# SJ2088POE_LEFT_OV9282.net
KiCad netlist of a schematic drawn in Altium Designer
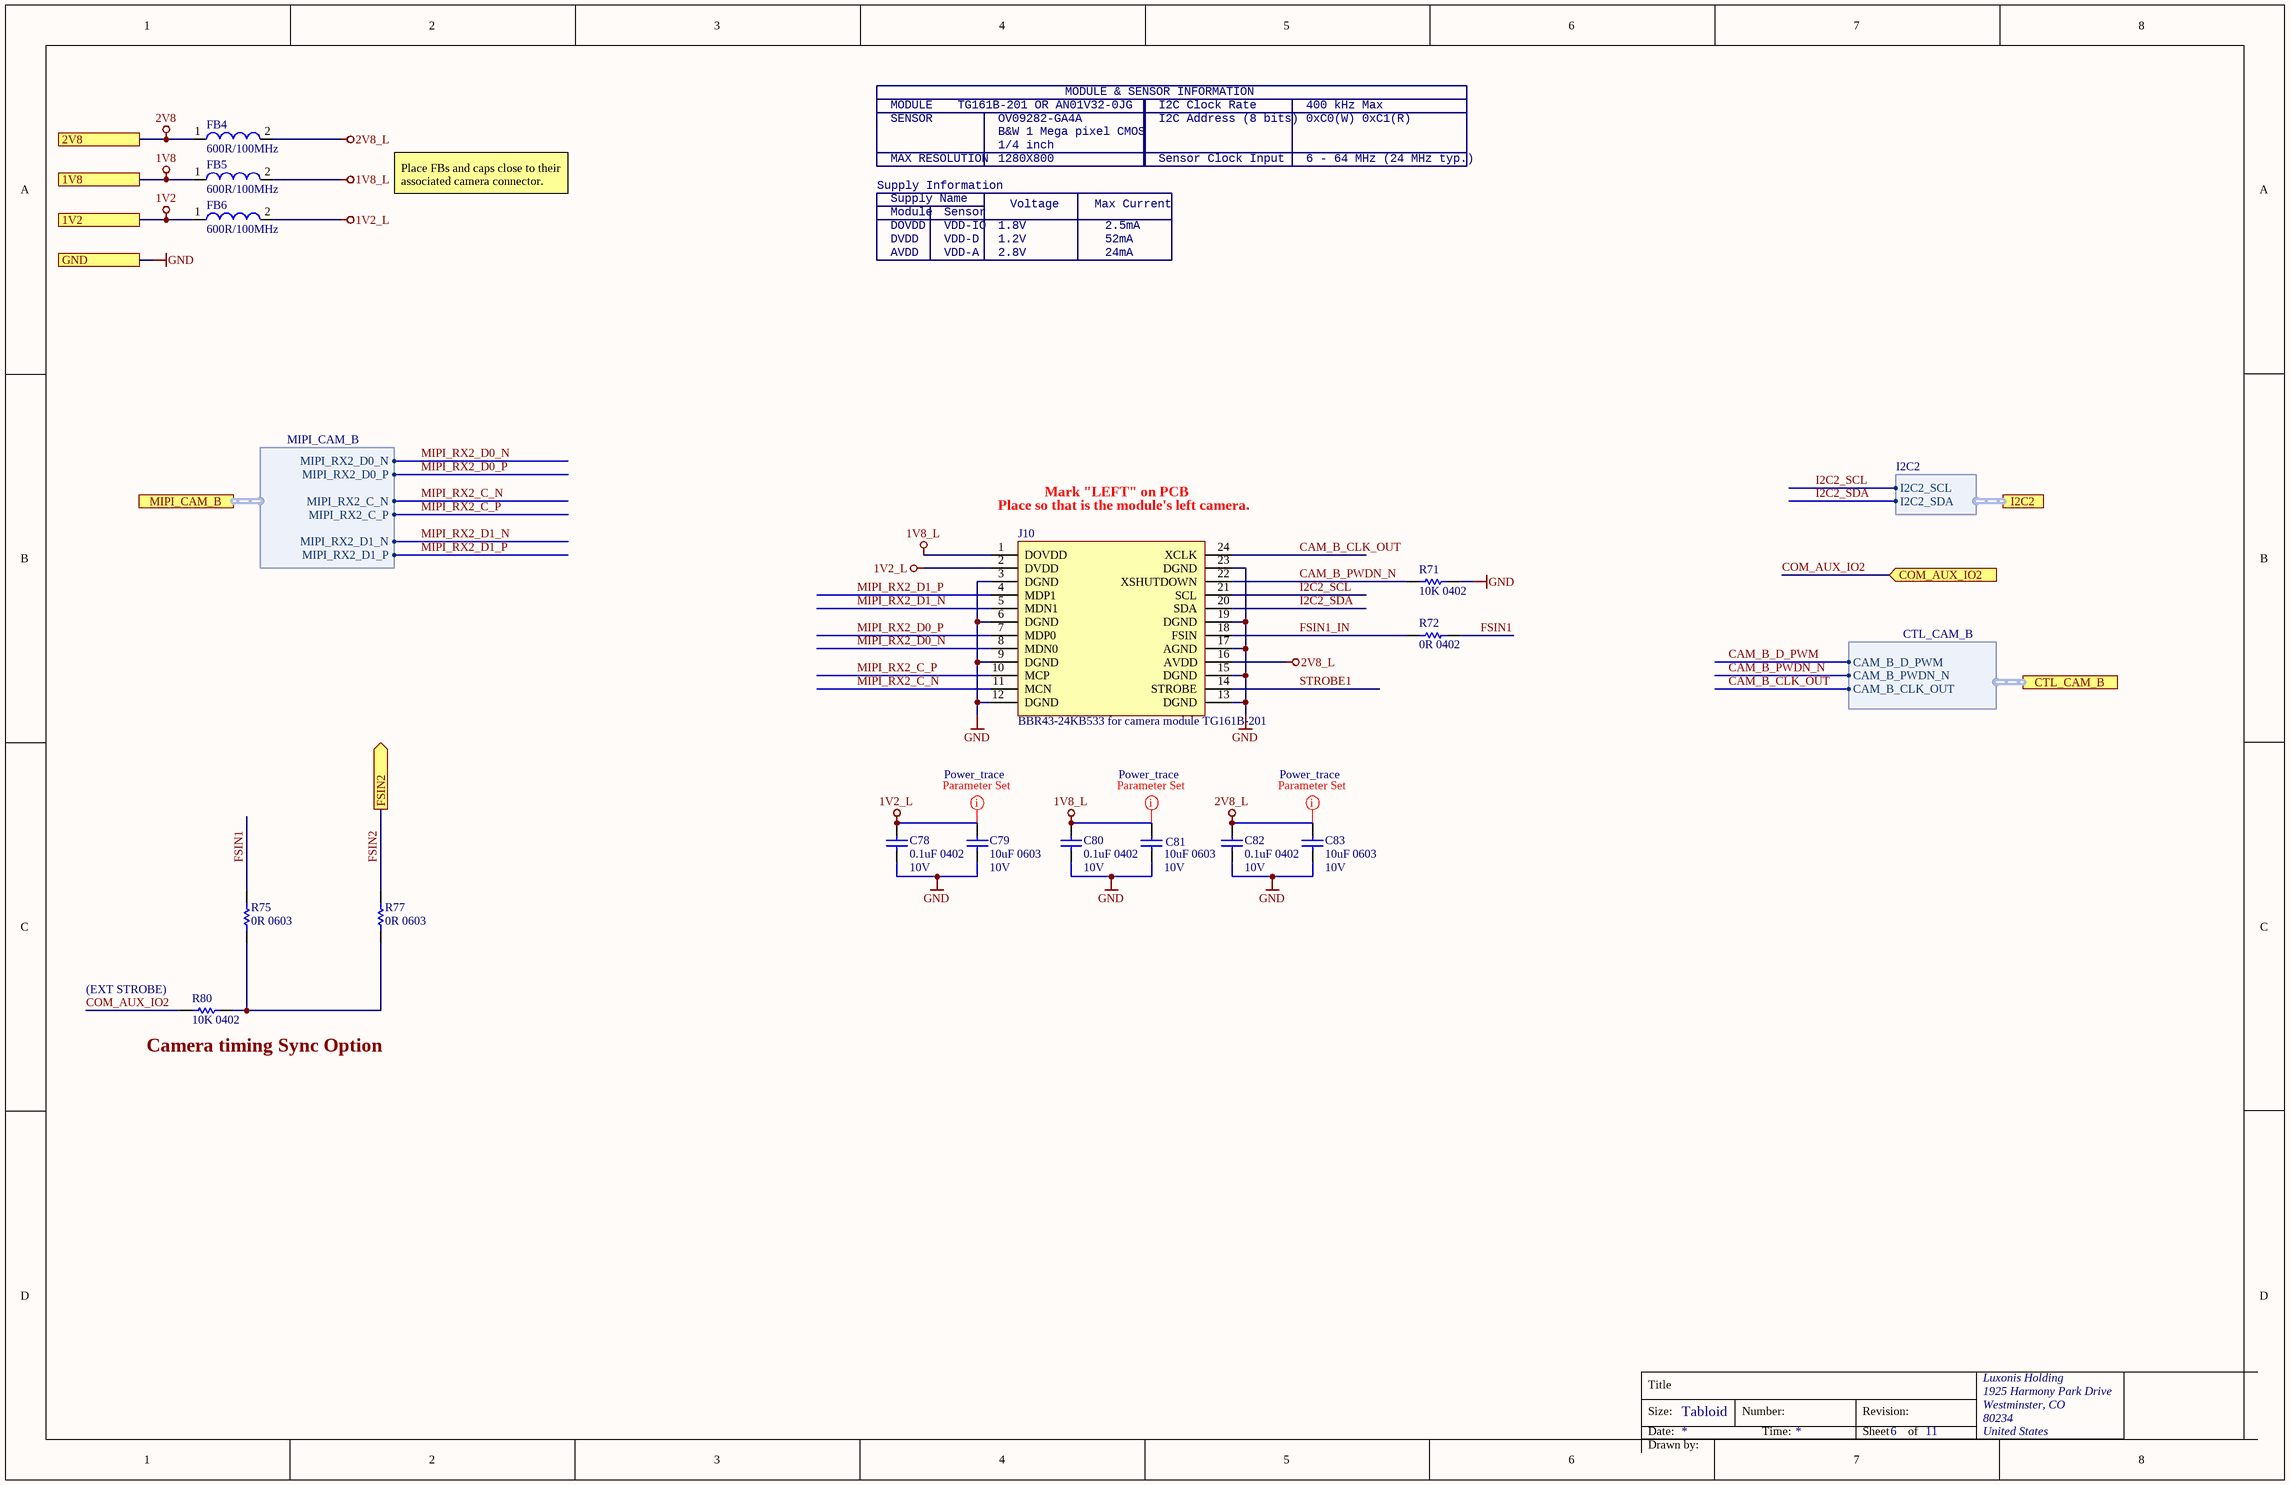
[diagram p0: SJ2088POE_LEFT_OV9282.SchDoc]

(export (version "E")
  (design (tool "Eeschema 10.0.6"))
  (components
    (comp (ref "C78")
      (value "0.1uF 0402")
      (footprint "CAP_Altium_Vault_Generic:CAPC0402(1005)70_L")
      (description "CAP CER 0.1UF 10V X7R 0402 5%")
      (fields (field (name "TOLERANCE") "5%") (field (name "VOLTAGE RATING") "10V"))
      (libsource (lib "LuxonisMaster") (part "GRM155R71A104JA01D"))
    )
    (comp (ref "C79")
      (value "10uF 0603")
      (footprint "CAP_Altium_Vault_Generic:CAPC0603(1608)100_L")
      (description "CAP CER 10UF 10V X5R 0603 20%")
      (fields (field (name "TOLERANCE") "20%") (field (name "VOLTAGE RATING") "10V"))
      (libsource (lib "LuxonisMaster") (part "GRM188R61A106ME69D"))
    )
    (comp (ref "C80")
      (value "0.1uF 0402")
      (footprint "CAP_Altium_Vault_Generic:CAPC0402(1005)70_L")
      (description "CAP CER 0.1UF 10V X7R 0402 5%")
      (fields (field (name "TOLERANCE") "5%") (field (name "VOLTAGE RATING") "10V"))
      (libsource (lib "LuxonisMaster") (part "GRM155R71A104JA01D"))
    )
    (comp (ref "C81")
      (value "10uF 0603")
      (footprint "CAP_Altium_Vault_Generic:CAPC0603(1608)100_L")
      (description "CAP CER 10UF 10V X5R 0603 20%")
      (fields (field (name "TOLERANCE") "20%") (field (name "VOLTAGE RATING") "10V"))
      (libsource (lib "LuxonisMaster") (part "GRM188R61A106ME69D"))
    )
    (comp (ref "C82")
      (value "0.1uF 0402")
      (footprint "CAP_Altium_Vault_Generic:CAPC0402(1005)70_L")
      (description "CAP CER 0.1UF 10V X7R 0402 5%")
      (fields (field (name "TOLERANCE") "5%") (field (name "VOLTAGE RATING") "10V"))
      (libsource (lib "LuxonisMaster") (part "GRM155R71A104JA01D"))
    )
    (comp (ref "C83")
      (value "10uF 0603")
      (footprint "CAP_Altium_Vault_Generic:CAPC0603(1608)100_L")
      (description "CAP CER 10UF 10V X5R 0603 20%")
      (fields (field (name "TOLERANCE") "20%") (field (name "VOLTAGE RATING") "10V"))
      (libsource (lib "LuxonisMaster") (part "GRM188R61A106ME69D"))
    )
    (comp (ref "FB4")
      (value "600R/100MHz")
      (footprint "LuxonisMaster:2508056017Y2")
      (description "FERRITE BEAD, 0.1OHM, 2A, 0805, 600R/100MHz")
      (fields (field (name "TOLERANCE") "25%"))
      (libsource (lib "LuxonisMaster") (part "2508056017Y2"))
    )
    (comp (ref "FB5")
      (value "600R/100MHz")
      (footprint "LuxonisMaster:2508056017Y2")
      (description "FERRITE BEAD, 0.1OHM, 2A, 0805, 600R/100MHz")
      (fields (field (name "TOLERANCE") "25%"))
      (libsource (lib "LuxonisMaster") (part "2508056017Y2"))
    )
    (comp (ref "FB6")
      (value "600R/100MHz")
      (footprint "LuxonisMaster:2508056017Y2")
      (description "FERRITE BEAD, 0.1OHM, 2A, 0805, 600R/100MHz")
      (fields (field (name "TOLERANCE") "25%"))
      (libsource (lib "LuxonisMaster") (part "2508056017Y2"))
    )
    (comp (ref "J10")
      (value "BBR43-24KB533 for camera module TG161B-201")
      (footprint "LuxonisMaster:TG161B-201 / AN01V32 - Board Wrap (7mm setback) MinPads")
      (description "CONN 24 way, 2 row board to board connector SMD")
      (libsource (lib "LuxonisMaster") (part "TG161B-201_Connector"))
    )
    (comp (ref "R71")
      (value "10K 0402")
      (footprint "RES_Altium_Vault_Generic:RESC0402(1005)_L")
      (fields (field (name "TOLERANCE") "1%"))
      (libsource (lib "LuxonisMaster") (part "RC0402FR-1310KL"))
    )
    (comp (ref "R72")
      (value "0R 0402")
      (footprint "RES_Altium_Vault_Generic:RESC0402(1005)_L")
      (description "RES SMD 0 OHM JUMPER 1/16W 0402")
      (fields (field (name "TOLERANCE") "5%"))
      (libsource (lib "LuxonisMaster") (part "CRCW04020000Z0ED"))
    )
    (comp (ref "R75")
      (value "0R 0603")
      (footprint "RES_Altium_Vault_Generic:RESC0603(1608)_N")
      (fields (field (name "TOLERANCE") "5%"))
      (libsource (lib "LuxonisMaster") (part "CRCW06030000Z0EA"))
    )
    (comp (ref "R77")
      (value "0R 0603")
      (footprint "RES_Altium_Vault_Generic:RESC0603(1608)_N")
      (fields (field (name "TOLERANCE") "5%"))
      (libsource (lib "LuxonisMaster") (part "CRCW06030000Z0EA"))
    )
    (comp (ref "R80")
      (value "10K 0402")
      (footprint "RES_Altium_Vault_Generic:RESC0402(1005)_L")
      (fields (field (name "TOLERANCE") "1%"))
      (libsource (lib "LuxonisMaster") (part "RC0402FR-1310KL"))
    )
  )
  (nets
    (net (code "4") (name "/CAM_B_CLK_OUT") (class "Default")
      (node (ref "J10") (pin "24") (pinfunction "XCLK_24") (pintype "passive"))
    )
    (net (code "6") (name "/CAM_B_PWDN_N") (class "Default")
      (node (ref "J10") (pin "22") (pinfunction "XSHUTDOWN_22") (pintype "passive"))
      (node (ref "R71") (pin "1") (pinfunction "1_1") (pintype "passive"))
    )
    (net (code "7") (name "/COM_AUX_IO2") (class "Default")
      (node (ref "R80") (pin "1") (pinfunction "1_1") (pintype "passive"))
    )
    (net (code "8") (name "/FSIN1") (class "Default")
      (node (ref "R72") (pin "2") (pinfunction "2_2") (pintype "passive"))
      (node (ref "R75") (pin "2") (pinfunction "2_2") (pintype "passive"))
    )
    (net (code "9") (name "/FSIN1_IN") (class "Default")
      (node (ref "J10") (pin "18") (pinfunction "FSIN_18") (pintype "passive"))
      (node (ref "R72") (pin "1") (pinfunction "1_1") (pintype "passive"))
    )
    (net (code "10") (name "/FSIN2") (class "Default")
      (node (ref "R77") (pin "2") (pinfunction "2_2") (pintype "passive"))
    )
    (net (code "11") (name "/I2C2_SCL") (class "Default")
      (node (ref "J10") (pin "21") (pinfunction "SCL_21") (pintype "passive"))
    )
    (net (code "12") (name "/I2C2_SDA") (class "Default")
      (node (ref "J10") (pin "20") (pinfunction "SDA_20") (pintype "passive"))
    )
    (net (code "13") (name "/MIPI_RX2_C_N") (class "Default")
      (node (ref "J10") (pin "11") (pinfunction "MCN_11") (pintype "passive"))
    )
    (net (code "14") (name "/MIPI_RX2_C_P") (class "Default")
      (node (ref "J10") (pin "10") (pinfunction "MCP_10") (pintype "passive"))
    )
    (net (code "15") (name "/MIPI_RX2_D0_N") (class "Default")
      (node (ref "J10") (pin "8") (pinfunction "MDN0_8") (pintype "passive"))
    )
    (net (code "16") (name "/MIPI_RX2_D0_P") (class "Default")
      (node (ref "J10") (pin "7") (pinfunction "MDP0_7") (pintype "passive"))
    )
    (net (code "17") (name "/MIPI_RX2_D1_N") (class "Default")
      (node (ref "J10") (pin "5") (pinfunction "MDN1_5") (pintype "passive"))
    )
    (net (code "18") (name "/MIPI_RX2_D1_P") (class "Default")
      (node (ref "J10") (pin "4") (pinfunction "MDP1_4") (pintype "passive"))
    )
    (net (code "19") (name "/STROBE1") (class "Default")
      (node (ref "J10") (pin "14") (pinfunction "STROBE_14") (pintype "passive"))
    )
    (net (code "23") (name "1V2") (class "Default")
      (node (ref "FB6") (pin "1") (pinfunction "1_1") (pintype "passive"))
    )
    (net (code "24") (name "1V2_L") (class "Default")
      (node (ref "C78") (pin "2") (pinfunction "2_2") (pintype "passive"))
      (node (ref "C79") (pin "2") (pinfunction "2_2") (pintype "passive"))
      (node (ref "FB6") (pin "2") (pinfunction "2_2") (pintype "passive"))
      (node (ref "J10") (pin "2") (pinfunction "DVDD_2") (pintype "passive"))
    )
    (net (code "25") (name "1V8") (class "Default")
      (node (ref "FB5") (pin "1") (pinfunction "1_1") (pintype "passive"))
    )
    (net (code "26") (name "1V8_L") (class "Default")
      (node (ref "C80") (pin "2") (pinfunction "2_2") (pintype "passive"))
      (node (ref "C81") (pin "2") (pinfunction "2_2") (pintype "passive"))
      (node (ref "FB5") (pin "2") (pinfunction "2_2") (pintype "passive"))
      (node (ref "J10") (pin "1") (pinfunction "DOVDD_1") (pintype "passive"))
    )
    (net (code "27") (name "2V8") (class "Default")
      (node (ref "FB4") (pin "1") (pinfunction "1_1") (pintype "passive"))
    )
    (net (code "28") (name "2V8_L") (class "Default")
      (node (ref "C82") (pin "2") (pinfunction "2_2") (pintype "passive"))
      (node (ref "C83") (pin "2") (pinfunction "2_2") (pintype "passive"))
      (node (ref "FB4") (pin "2") (pinfunction "2_2") (pintype "passive"))
      (node (ref "J10") (pin "16") (pinfunction "AVDD_16") (pintype "passive"))
    )
    (net (code "29") (name "GND") (class "Default")
      (node (ref "C78") (pin "1") (pinfunction "1_1") (pintype "passive"))
      (node (ref "C79") (pin "1") (pinfunction "1_1") (pintype "passive"))
      (node (ref "C80") (pin "1") (pinfunction "1_1") (pintype "passive"))
      (node (ref "C81") (pin "1") (pinfunction "1_1") (pintype "passive"))
      (node (ref "C82") (pin "1") (pinfunction "1_1") (pintype "passive"))
      (node (ref "C83") (pin "1") (pinfunction "1_1") (pintype "passive"))
      (node (ref "J10") (pin "12") (pinfunction "DGND_12") (pintype "passive"))
      (node (ref "J10") (pin "13") (pinfunction "DGND_13") (pintype "passive"))
      (node (ref "J10") (pin "15") (pinfunction "DGND_15") (pintype "passive"))
      (node (ref "J10") (pin "17") (pinfunction "AGND_17") (pintype "passive"))
      (node (ref "J10") (pin "19") (pinfunction "DGND_19") (pintype "passive"))
      (node (ref "J10") (pin "23") (pinfunction "DGND_23") (pintype "passive"))
      (node (ref "J10") (pin "3") (pinfunction "DGND_3") (pintype "passive"))
      (node (ref "J10") (pin "6") (pinfunction "DGND_6") (pintype "passive"))
      (node (ref "J10") (pin "9") (pinfunction "DGND_9") (pintype "passive"))
      (node (ref "R71") (pin "2") (pinfunction "2_2") (pintype "passive"))
    )
    (net (code "30") (name "Net-(R75-Pad1)") (class "Default")
      (node (ref "R75") (pin "1") (pinfunction "1_1") (pintype "passive"))
      (node (ref "R77") (pin "1") (pinfunction "1_1") (pintype "passive"))
      (node (ref "R80") (pin "2") (pinfunction "2_2") (pintype "passive"))
    )
  )
)
